# board.net
KiCad netlist of a schematic drawn in EAGLE
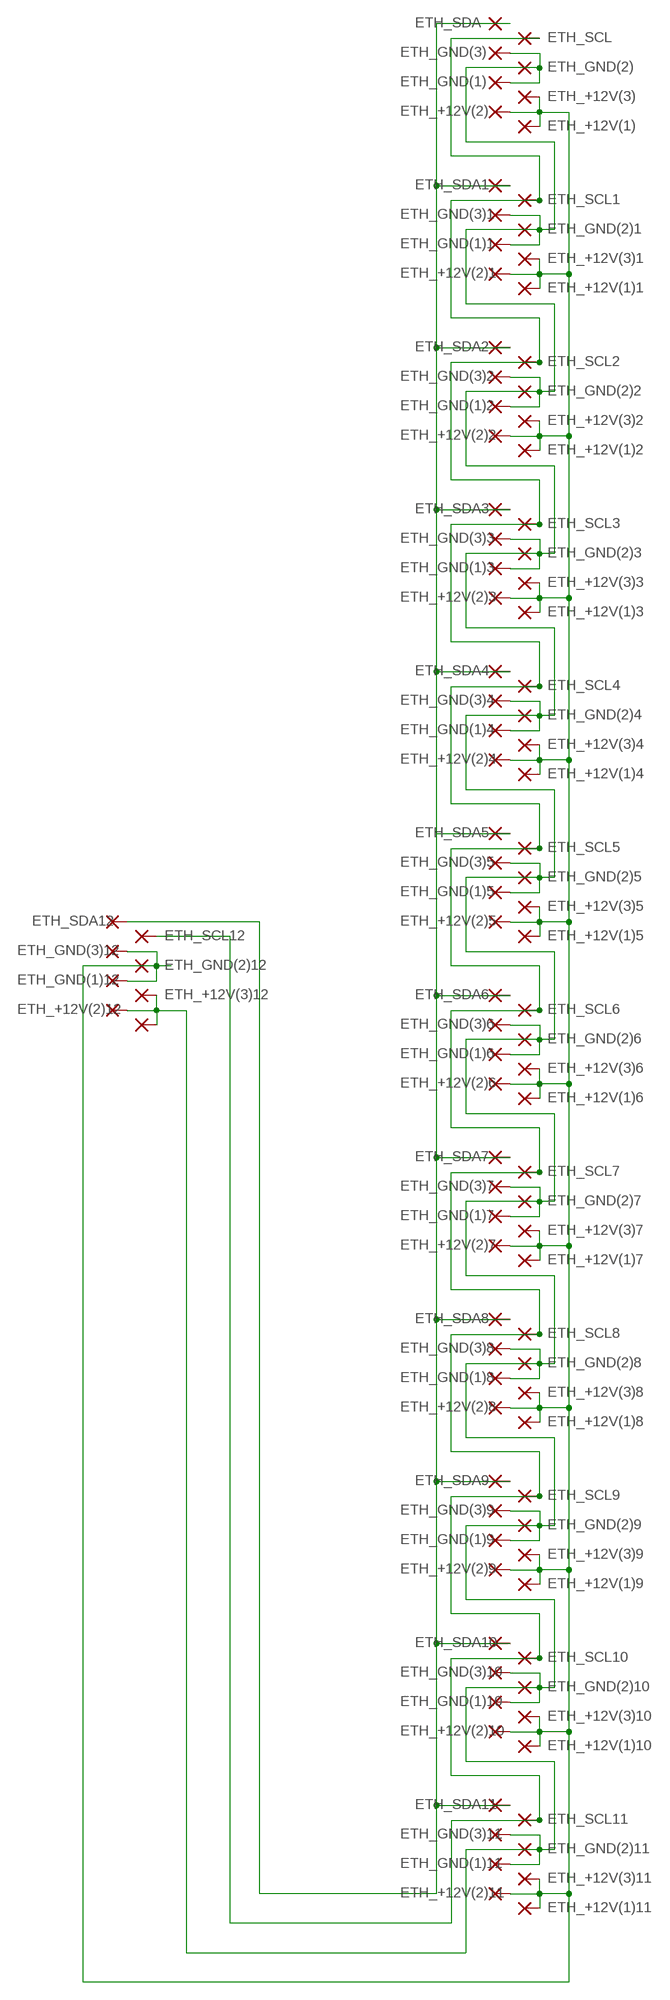
[diagram p0: schematic, sheet 1]

(export (version "E")
  (design (tool "Eeschema 10.0.6"))
  (components
    (comp (ref "ETH_+12V(1)")
      (value "2,15/1,0")
      (footprint "eagle-import:2,15_1,0")
      (libsource (lib "eagle-import") (part "2,15/1,0"))
    )
    (comp (ref "ETH_+12V(1)1")
      (value "2,15/1,0")
      (footprint "eagle-import:2,15_1,0")
      (libsource (lib "eagle-import") (part "2,15/1,0"))
    )
    (comp (ref "ETH_+12V(1)2")
      (value "2,15/1,0")
      (footprint "eagle-import:2,15_1,0")
      (libsource (lib "eagle-import") (part "2,15/1,0"))
    )
    (comp (ref "ETH_+12V(1)3")
      (value "2,15/1,0")
      (footprint "eagle-import:2,15_1,0")
      (libsource (lib "eagle-import") (part "2,15/1,0"))
    )
    (comp (ref "ETH_+12V(1)4")
      (value "2,15/1,0")
      (footprint "eagle-import:2,15_1,0")
      (libsource (lib "eagle-import") (part "2,15/1,0"))
    )
    (comp (ref "ETH_+12V(1)5")
      (value "2,15/1,0")
      (footprint "eagle-import:2,15_1,0")
      (libsource (lib "eagle-import") (part "2,15/1,0"))
    )
    (comp (ref "ETH_+12V(1)6")
      (value "2,15/1,0")
      (footprint "eagle-import:2,15_1,0")
      (libsource (lib "eagle-import") (part "2,15/1,0"))
    )
    (comp (ref "ETH_+12V(1)7")
      (value "2,15/1,0")
      (footprint "eagle-import:2,15_1,0")
      (libsource (lib "eagle-import") (part "2,15/1,0"))
    )
    (comp (ref "ETH_+12V(1)8")
      (value "2,15/1,0")
      (footprint "eagle-import:2,15_1,0")
      (libsource (lib "eagle-import") (part "2,15/1,0"))
    )
    (comp (ref "ETH_+12V(1)9")
      (value "2,15/1,0")
      (footprint "eagle-import:2,15_1,0")
      (libsource (lib "eagle-import") (part "2,15/1,0"))
    )
    (comp (ref "ETH_+12V(1)10")
      (value "2,15/1,0")
      (footprint "eagle-import:2,15_1,0")
      (libsource (lib "eagle-import") (part "2,15/1,0"))
    )
    (comp (ref "ETH_+12V(1)11")
      (value "2,15/1,0")
      (footprint "eagle-import:2,15_1,0")
      (libsource (lib "eagle-import") (part "2,15/1,0"))
    )
    (comp (ref "ETH_+12V(1)12")
      (value "2,15/1,0")
      (footprint "eagle-import:2,15_1,0")
      (libsource (lib "eagle-import") (part "2,15/1,0"))
    )
    (comp (ref "ETH_+12V(2)")
      (value "2,15/1,0")
      (footprint "eagle-import:2,15_1,0")
      (libsource (lib "eagle-import") (part "2,15/1,0"))
    )
    (comp (ref "ETH_+12V(2)1")
      (value "2,15/1,0")
      (footprint "eagle-import:2,15_1,0")
      (libsource (lib "eagle-import") (part "2,15/1,0"))
    )
    (comp (ref "ETH_+12V(2)2")
      (value "2,15/1,0")
      (footprint "eagle-import:2,15_1,0")
      (libsource (lib "eagle-import") (part "2,15/1,0"))
    )
    (comp (ref "ETH_+12V(2)3")
      (value "2,15/1,0")
      (footprint "eagle-import:2,15_1,0")
      (libsource (lib "eagle-import") (part "2,15/1,0"))
    )
    (comp (ref "ETH_+12V(2)4")
      (value "2,15/1,0")
      (footprint "eagle-import:2,15_1,0")
      (libsource (lib "eagle-import") (part "2,15/1,0"))
    )
    (comp (ref "ETH_+12V(2)5")
      (value "2,15/1,0")
      (footprint "eagle-import:2,15_1,0")
      (libsource (lib "eagle-import") (part "2,15/1,0"))
    )
    (comp (ref "ETH_+12V(2)6")
      (value "2,15/1,0")
      (footprint "eagle-import:2,15_1,0")
      (libsource (lib "eagle-import") (part "2,15/1,0"))
    )
    (comp (ref "ETH_+12V(2)7")
      (value "2,15/1,0")
      (footprint "eagle-import:2,15_1,0")
      (libsource (lib "eagle-import") (part "2,15/1,0"))
    )
    (comp (ref "ETH_+12V(2)8")
      (value "2,15/1,0")
      (footprint "eagle-import:2,15_1,0")
      (libsource (lib "eagle-import") (part "2,15/1,0"))
    )
    (comp (ref "ETH_+12V(2)9")
      (value "2,15/1,0")
      (footprint "eagle-import:2,15_1,0")
      (libsource (lib "eagle-import") (part "2,15/1,0"))
    )
    (comp (ref "ETH_+12V(2)10")
      (value "2,15/1,0")
      (footprint "eagle-import:2,15_1,0")
      (libsource (lib "eagle-import") (part "2,15/1,0"))
    )
    (comp (ref "ETH_+12V(2)11")
      (value "2,15/1,0")
      (footprint "eagle-import:2,15_1,0")
      (libsource (lib "eagle-import") (part "2,15/1,0"))
    )
    (comp (ref "ETH_+12V(2)12")
      (value "2,15/1,0")
      (footprint "eagle-import:2,15_1,0")
      (libsource (lib "eagle-import") (part "2,15/1,0"))
    )
    (comp (ref "ETH_+12V(3)")
      (value "2,15/1,0")
      (footprint "eagle-import:2,15_1,0")
      (libsource (lib "eagle-import") (part "2,15/1,0"))
    )
    (comp (ref "ETH_+12V(3)1")
      (value "2,15/1,0")
      (footprint "eagle-import:2,15_1,0")
      (libsource (lib "eagle-import") (part "2,15/1,0"))
    )
    (comp (ref "ETH_+12V(3)2")
      (value "2,15/1,0")
      (footprint "eagle-import:2,15_1,0")
      (libsource (lib "eagle-import") (part "2,15/1,0"))
    )
    (comp (ref "ETH_+12V(3)3")
      (value "2,15/1,0")
      (footprint "eagle-import:2,15_1,0")
      (libsource (lib "eagle-import") (part "2,15/1,0"))
    )
    (comp (ref "ETH_+12V(3)4")
      (value "2,15/1,0")
      (footprint "eagle-import:2,15_1,0")
      (libsource (lib "eagle-import") (part "2,15/1,0"))
    )
    (comp (ref "ETH_+12V(3)5")
      (value "2,15/1,0")
      (footprint "eagle-import:2,15_1,0")
      (libsource (lib "eagle-import") (part "2,15/1,0"))
    )
    (comp (ref "ETH_+12V(3)6")
      (value "2,15/1,0")
      (footprint "eagle-import:2,15_1,0")
      (libsource (lib "eagle-import") (part "2,15/1,0"))
    )
    (comp (ref "ETH_+12V(3)7")
      (value "2,15/1,0")
      (footprint "eagle-import:2,15_1,0")
      (libsource (lib "eagle-import") (part "2,15/1,0"))
    )
    (comp (ref "ETH_+12V(3)8")
      (value "2,15/1,0")
      (footprint "eagle-import:2,15_1,0")
      (libsource (lib "eagle-import") (part "2,15/1,0"))
    )
    (comp (ref "ETH_+12V(3)9")
      (value "2,15/1,0")
      (footprint "eagle-import:2,15_1,0")
      (libsource (lib "eagle-import") (part "2,15/1,0"))
    )
    (comp (ref "ETH_+12V(3)10")
      (value "2,15/1,0")
      (footprint "eagle-import:2,15_1,0")
      (libsource (lib "eagle-import") (part "2,15/1,0"))
    )
    (comp (ref "ETH_+12V(3)11")
      (value "2,15/1,0")
      (footprint "eagle-import:2,15_1,0")
      (libsource (lib "eagle-import") (part "2,15/1,0"))
    )
    (comp (ref "ETH_+12V(3)12")
      (value "2,15/1,0")
      (footprint "eagle-import:2,15_1,0")
      (libsource (lib "eagle-import") (part "2,15/1,0"))
    )
    (comp (ref "ETH_GND(1)")
      (value "2,15/1,0")
      (footprint "eagle-import:2,15_1,0")
      (libsource (lib "eagle-import") (part "2,15/1,0"))
    )
    (comp (ref "ETH_GND(1)1")
      (value "2,15/1,0")
      (footprint "eagle-import:2,15_1,0")
      (libsource (lib "eagle-import") (part "2,15/1,0"))
    )
    (comp (ref "ETH_GND(1)2")
      (value "2,15/1,0")
      (footprint "eagle-import:2,15_1,0")
      (libsource (lib "eagle-import") (part "2,15/1,0"))
    )
    (comp (ref "ETH_GND(1)3")
      (value "2,15/1,0")
      (footprint "eagle-import:2,15_1,0")
      (libsource (lib "eagle-import") (part "2,15/1,0"))
    )
    (comp (ref "ETH_GND(1)4")
      (value "2,15/1,0")
      (footprint "eagle-import:2,15_1,0")
      (libsource (lib "eagle-import") (part "2,15/1,0"))
    )
    (comp (ref "ETH_GND(1)5")
      (value "2,15/1,0")
      (footprint "eagle-import:2,15_1,0")
      (libsource (lib "eagle-import") (part "2,15/1,0"))
    )
    (comp (ref "ETH_GND(1)6")
      (value "2,15/1,0")
      (footprint "eagle-import:2,15_1,0")
      (libsource (lib "eagle-import") (part "2,15/1,0"))
    )
    (comp (ref "ETH_GND(1)7")
      (value "2,15/1,0")
      (footprint "eagle-import:2,15_1,0")
      (libsource (lib "eagle-import") (part "2,15/1,0"))
    )
    (comp (ref "ETH_GND(1)8")
      (value "2,15/1,0")
      (footprint "eagle-import:2,15_1,0")
      (libsource (lib "eagle-import") (part "2,15/1,0"))
    )
    (comp (ref "ETH_GND(1)9")
      (value "2,15/1,0")
      (footprint "eagle-import:2,15_1,0")
      (libsource (lib "eagle-import") (part "2,15/1,0"))
    )
    (comp (ref "ETH_GND(1)10")
      (value "2,15/1,0")
      (footprint "eagle-import:2,15_1,0")
      (libsource (lib "eagle-import") (part "2,15/1,0"))
    )
    (comp (ref "ETH_GND(1)11")
      (value "2,15/1,0")
      (footprint "eagle-import:2,15_1,0")
      (libsource (lib "eagle-import") (part "2,15/1,0"))
    )
    (comp (ref "ETH_GND(1)12")
      (value "2,15/1,0")
      (footprint "eagle-import:2,15_1,0")
      (libsource (lib "eagle-import") (part "2,15/1,0"))
    )
    (comp (ref "ETH_GND(2)")
      (value "2,15/1,0")
      (footprint "eagle-import:2,15_1,0")
      (libsource (lib "eagle-import") (part "2,15/1,0"))
    )
    (comp (ref "ETH_GND(2)1")
      (value "2,15/1,0")
      (footprint "eagle-import:2,15_1,0")
      (libsource (lib "eagle-import") (part "2,15/1,0"))
    )
    (comp (ref "ETH_GND(2)2")
      (value "2,15/1,0")
      (footprint "eagle-import:2,15_1,0")
      (libsource (lib "eagle-import") (part "2,15/1,0"))
    )
    (comp (ref "ETH_GND(2)3")
      (value "2,15/1,0")
      (footprint "eagle-import:2,15_1,0")
      (libsource (lib "eagle-import") (part "2,15/1,0"))
    )
    (comp (ref "ETH_GND(2)4")
      (value "2,15/1,0")
      (footprint "eagle-import:2,15_1,0")
      (libsource (lib "eagle-import") (part "2,15/1,0"))
    )
    (comp (ref "ETH_GND(2)5")
      (value "2,15/1,0")
      (footprint "eagle-import:2,15_1,0")
      (libsource (lib "eagle-import") (part "2,15/1,0"))
    )
    (comp (ref "ETH_GND(2)6")
      (value "2,15/1,0")
      (footprint "eagle-import:2,15_1,0")
      (libsource (lib "eagle-import") (part "2,15/1,0"))
    )
    (comp (ref "ETH_GND(2)7")
      (value "2,15/1,0")
      (footprint "eagle-import:2,15_1,0")
      (libsource (lib "eagle-import") (part "2,15/1,0"))
    )
    (comp (ref "ETH_GND(2)8")
      (value "2,15/1,0")
      (footprint "eagle-import:2,15_1,0")
      (libsource (lib "eagle-import") (part "2,15/1,0"))
    )
    (comp (ref "ETH_GND(2)9")
      (value "2,15/1,0")
      (footprint "eagle-import:2,15_1,0")
      (libsource (lib "eagle-import") (part "2,15/1,0"))
    )
    (comp (ref "ETH_GND(2)10")
      (value "2,15/1,0")
      (footprint "eagle-import:2,15_1,0")
      (libsource (lib "eagle-import") (part "2,15/1,0"))
    )
    (comp (ref "ETH_GND(2)11")
      (value "2,15/1,0")
      (footprint "eagle-import:2,15_1,0")
      (libsource (lib "eagle-import") (part "2,15/1,0"))
    )
    (comp (ref "ETH_GND(2)12")
      (value "2,15/1,0")
      (footprint "eagle-import:2,15_1,0")
      (libsource (lib "eagle-import") (part "2,15/1,0"))
    )
    (comp (ref "ETH_GND(3)")
      (value "2,15/1,0")
      (footprint "eagle-import:2,15_1,0")
      (libsource (lib "eagle-import") (part "2,15/1,0"))
    )
    (comp (ref "ETH_GND(3)1")
      (value "2,15/1,0")
      (footprint "eagle-import:2,15_1,0")
      (libsource (lib "eagle-import") (part "2,15/1,0"))
    )
    (comp (ref "ETH_GND(3)2")
      (value "2,15/1,0")
      (footprint "eagle-import:2,15_1,0")
      (libsource (lib "eagle-import") (part "2,15/1,0"))
    )
    (comp (ref "ETH_GND(3)3")
      (value "2,15/1,0")
      (footprint "eagle-import:2,15_1,0")
      (libsource (lib "eagle-import") (part "2,15/1,0"))
    )
    (comp (ref "ETH_GND(3)4")
      (value "2,15/1,0")
      (footprint "eagle-import:2,15_1,0")
      (libsource (lib "eagle-import") (part "2,15/1,0"))
    )
    (comp (ref "ETH_GND(3)5")
      (value "2,15/1,0")
      (footprint "eagle-import:2,15_1,0")
      (libsource (lib "eagle-import") (part "2,15/1,0"))
    )
    (comp (ref "ETH_GND(3)6")
      (value "2,15/1,0")
      (footprint "eagle-import:2,15_1,0")
      (libsource (lib "eagle-import") (part "2,15/1,0"))
    )
    (comp (ref "ETH_GND(3)7")
      (value "2,15/1,0")
      (footprint "eagle-import:2,15_1,0")
      (libsource (lib "eagle-import") (part "2,15/1,0"))
    )
    (comp (ref "ETH_GND(3)8")
      (value "2,15/1,0")
      (footprint "eagle-import:2,15_1,0")
      (libsource (lib "eagle-import") (part "2,15/1,0"))
    )
    (comp (ref "ETH_GND(3)9")
      (value "2,15/1,0")
      (footprint "eagle-import:2,15_1,0")
      (libsource (lib "eagle-import") (part "2,15/1,0"))
    )
    (comp (ref "ETH_GND(3)10")
      (value "2,15/1,0")
      (footprint "eagle-import:2,15_1,0")
      (libsource (lib "eagle-import") (part "2,15/1,0"))
    )
    (comp (ref "ETH_GND(3)11")
      (value "2,15/1,0")
      (footprint "eagle-import:2,15_1,0")
      (libsource (lib "eagle-import") (part "2,15/1,0"))
    )
    (comp (ref "ETH_GND(3)12")
      (value "2,15/1,0")
      (footprint "eagle-import:2,15_1,0")
      (libsource (lib "eagle-import") (part "2,15/1,0"))
    )
    (comp (ref "ETH_SCL")
      (value "2,15/1,0")
      (footprint "eagle-import:2,15_1,0")
      (libsource (lib "eagle-import") (part "2,15/1,0"))
    )
    (comp (ref "ETH_SCL1")
      (value "2,15/1,0")
      (footprint "eagle-import:2,15_1,0")
      (libsource (lib "eagle-import") (part "2,15/1,0"))
    )
    (comp (ref "ETH_SCL2")
      (value "2,15/1,0")
      (footprint "eagle-import:2,15_1,0")
      (libsource (lib "eagle-import") (part "2,15/1,0"))
    )
    (comp (ref "ETH_SCL3")
      (value "2,15/1,0")
      (footprint "eagle-import:2,15_1,0")
      (libsource (lib "eagle-import") (part "2,15/1,0"))
    )
    (comp (ref "ETH_SCL4")
      (value "2,15/1,0")
      (footprint "eagle-import:2,15_1,0")
      (libsource (lib "eagle-import") (part "2,15/1,0"))
    )
    (comp (ref "ETH_SCL5")
      (value "2,15/1,0")
      (footprint "eagle-import:2,15_1,0")
      (libsource (lib "eagle-import") (part "2,15/1,0"))
    )
    (comp (ref "ETH_SCL6")
      (value "2,15/1,0")
      (footprint "eagle-import:2,15_1,0")
      (libsource (lib "eagle-import") (part "2,15/1,0"))
    )
    (comp (ref "ETH_SCL7")
      (value "2,15/1,0")
      (footprint "eagle-import:2,15_1,0")
      (libsource (lib "eagle-import") (part "2,15/1,0"))
    )
    (comp (ref "ETH_SCL8")
      (value "2,15/1,0")
      (footprint "eagle-import:2,15_1,0")
      (libsource (lib "eagle-import") (part "2,15/1,0"))
    )
    (comp (ref "ETH_SCL9")
      (value "2,15/1,0")
      (footprint "eagle-import:2,15_1,0")
      (libsource (lib "eagle-import") (part "2,15/1,0"))
    )
    (comp (ref "ETH_SCL10")
      (value "2,15/1,0")
      (footprint "eagle-import:2,15_1,0")
      (libsource (lib "eagle-import") (part "2,15/1,0"))
    )
    (comp (ref "ETH_SCL11")
      (value "2,15/1,0")
      (footprint "eagle-import:2,15_1,0")
      (libsource (lib "eagle-import") (part "2,15/1,0"))
    )
    (comp (ref "ETH_SCL12")
      (value "2,15/1,0")
      (footprint "eagle-import:2,15_1,0")
      (libsource (lib "eagle-import") (part "2,15/1,0"))
    )
    (comp (ref "ETH_SDA")
      (value "2,15/1,0")
      (footprint "eagle-import:2,15_1,0")
      (libsource (lib "eagle-import") (part "2,15/1,0"))
    )
    (comp (ref "ETH_SDA1")
      (value "2,15/1,0")
      (footprint "eagle-import:2,15_1,0")
      (libsource (lib "eagle-import") (part "2,15/1,0"))
    )
    (comp (ref "ETH_SDA2")
      (value "2,15/1,0")
      (footprint "eagle-import:2,15_1,0")
      (libsource (lib "eagle-import") (part "2,15/1,0"))
    )
    (comp (ref "ETH_SDA3")
      (value "2,15/1,0")
      (footprint "eagle-import:2,15_1,0")
      (libsource (lib "eagle-import") (part "2,15/1,0"))
    )
    (comp (ref "ETH_SDA4")
      (value "2,15/1,0")
      (footprint "eagle-import:2,15_1,0")
      (libsource (lib "eagle-import") (part "2,15/1,0"))
    )
    (comp (ref "ETH_SDA5")
      (value "2,15/1,0")
      (footprint "eagle-import:2,15_1,0")
      (libsource (lib "eagle-import") (part "2,15/1,0"))
    )
    (comp (ref "ETH_SDA6")
      (value "2,15/1,0")
      (footprint "eagle-import:2,15_1,0")
      (libsource (lib "eagle-import") (part "2,15/1,0"))
    )
    (comp (ref "ETH_SDA7")
      (value "2,15/1,0")
      (footprint "eagle-import:2,15_1,0")
      (libsource (lib "eagle-import") (part "2,15/1,0"))
    )
    (comp (ref "ETH_SDA8")
      (value "2,15/1,0")
      (footprint "eagle-import:2,15_1,0")
      (libsource (lib "eagle-import") (part "2,15/1,0"))
    )
    (comp (ref "ETH_SDA9")
      (value "2,15/1,0")
      (footprint "eagle-import:2,15_1,0")
      (libsource (lib "eagle-import") (part "2,15/1,0"))
    )
    (comp (ref "ETH_SDA10")
      (value "2,15/1,0")
      (footprint "eagle-import:2,15_1,0")
      (libsource (lib "eagle-import") (part "2,15/1,0"))
    )
    (comp (ref "ETH_SDA11")
      (value "2,15/1,0")
      (footprint "eagle-import:2,15_1,0")
      (libsource (lib "eagle-import") (part "2,15/1,0"))
    )
    (comp (ref "ETH_SDA12")
      (value "2,15/1,0")
      (footprint "eagle-import:2,15_1,0")
      (libsource (lib "eagle-import") (part "2,15/1,0"))
    )
  )
  (nets
    (net (code "1") (name "Net-(ETH_+12V(1)-P)") (class "Default")
      (node (ref "ETH_+12V(1)") (pin "1") (pinfunction "P_1") (pintype "passive"))
      (node (ref "ETH_+12V(1)1") (pin "1") (pinfunction "P_1") (pintype "passive"))
      (node (ref "ETH_+12V(1)10") (pin "1") (pinfunction "P_1") (pintype "passive"))
      (node (ref "ETH_+12V(1)11") (pin "1") (pinfunction "P_1") (pintype "passive"))
      (node (ref "ETH_+12V(1)2") (pin "1") (pinfunction "P_1") (pintype "passive"))
      (node (ref "ETH_+12V(1)3") (pin "1") (pinfunction "P_1") (pintype "passive"))
      (node (ref "ETH_+12V(1)4") (pin "1") (pinfunction "P_1") (pintype "passive"))
      (node (ref "ETH_+12V(1)5") (pin "1") (pinfunction "P_1") (pintype "passive"))
      (node (ref "ETH_+12V(1)6") (pin "1") (pinfunction "P_1") (pintype "passive"))
      (node (ref "ETH_+12V(1)7") (pin "1") (pinfunction "P_1") (pintype "passive"))
      (node (ref "ETH_+12V(1)8") (pin "1") (pinfunction "P_1") (pintype "passive"))
      (node (ref "ETH_+12V(1)9") (pin "1") (pinfunction "P_1") (pintype "passive"))
      (node (ref "ETH_+12V(2)") (pin "1") (pinfunction "P_1") (pintype "passive"))
      (node (ref "ETH_+12V(2)1") (pin "1") (pinfunction "P_1") (pintype "passive"))
      (node (ref "ETH_+12V(2)10") (pin "1") (pinfunction "P_1") (pintype "passive"))
      (node (ref "ETH_+12V(2)11") (pin "1") (pinfunction "P_1") (pintype "passive"))
      (node (ref "ETH_+12V(2)2") (pin "1") (pinfunction "P_1") (pintype "passive"))
      (node (ref "ETH_+12V(2)3") (pin "1") (pinfunction "P_1") (pintype "passive"))
      (node (ref "ETH_+12V(2)4") (pin "1") (pinfunction "P_1") (pintype "passive"))
      (node (ref "ETH_+12V(2)5") (pin "1") (pinfunction "P_1") (pintype "passive"))
      (node (ref "ETH_+12V(2)6") (pin "1") (pinfunction "P_1") (pintype "passive"))
      (node (ref "ETH_+12V(2)7") (pin "1") (pinfunction "P_1") (pintype "passive"))
      (node (ref "ETH_+12V(2)8") (pin "1") (pinfunction "P_1") (pintype "passive"))
      (node (ref "ETH_+12V(2)9") (pin "1") (pinfunction "P_1") (pintype "passive"))
      (node (ref "ETH_+12V(3)") (pin "1") (pinfunction "P_1") (pintype "passive"))
      (node (ref "ETH_+12V(3)1") (pin "1") (pinfunction "P_1") (pintype "passive"))
      (node (ref "ETH_+12V(3)10") (pin "1") (pinfunction "P_1") (pintype "passive"))
      (node (ref "ETH_+12V(3)11") (pin "1") (pinfunction "P_1") (pintype "passive"))
      (node (ref "ETH_+12V(3)2") (pin "1") (pinfunction "P_1") (pintype "passive"))
      (node (ref "ETH_+12V(3)3") (pin "1") (pinfunction "P_1") (pintype "passive"))
      (node (ref "ETH_+12V(3)4") (pin "1") (pinfunction "P_1") (pintype "passive"))
      (node (ref "ETH_+12V(3)5") (pin "1") (pinfunction "P_1") (pintype "passive"))
      (node (ref "ETH_+12V(3)6") (pin "1") (pinfunction "P_1") (pintype "passive"))
      (node (ref "ETH_+12V(3)7") (pin "1") (pinfunction "P_1") (pintype "passive"))
      (node (ref "ETH_+12V(3)8") (pin "1") (pinfunction "P_1") (pintype "passive"))
      (node (ref "ETH_+12V(3)9") (pin "1") (pinfunction "P_1") (pintype "passive"))
      (node (ref "ETH_GND(1)12") (pin "1") (pinfunction "P_1") (pintype "passive"))
      (node (ref "ETH_GND(2)12") (pin "1") (pinfunction "P_1") (pintype "passive"))
      (node (ref "ETH_GND(3)12") (pin "1") (pinfunction "P_1") (pintype "passive"))
    )
    (net (code "2") (name "Net-(ETH_+12V(1)12-P)") (class "Default")
      (node (ref "ETH_+12V(1)12") (pin "1") (pinfunction "P_1") (pintype "passive"))
      (node (ref "ETH_+12V(2)12") (pin "1") (pinfunction "P_1") (pintype "passive"))
      (node (ref "ETH_+12V(3)12") (pin "1") (pinfunction "P_1") (pintype "passive"))
      (node (ref "ETH_GND(1)") (pin "1") (pinfunction "P_1") (pintype "passive"))
      (node (ref "ETH_GND(1)1") (pin "1") (pinfunction "P_1") (pintype "passive"))
      (node (ref "ETH_GND(1)10") (pin "1") (pinfunction "P_1") (pintype "passive"))
      (node (ref "ETH_GND(1)11") (pin "1") (pinfunction "P_1") (pintype "passive"))
      (node (ref "ETH_GND(1)2") (pin "1") (pinfunction "P_1") (pintype "passive"))
      (node (ref "ETH_GND(1)3") (pin "1") (pinfunction "P_1") (pintype "passive"))
      (node (ref "ETH_GND(1)4") (pin "1") (pinfunction "P_1") (pintype "passive"))
      (node (ref "ETH_GND(1)5") (pin "1") (pinfunction "P_1") (pintype "passive"))
      (node (ref "ETH_GND(1)6") (pin "1") (pinfunction "P_1") (pintype "passive"))
      (node (ref "ETH_GND(1)7") (pin "1") (pinfunction "P_1") (pintype "passive"))
      (node (ref "ETH_GND(1)8") (pin "1") (pinfunction "P_1") (pintype "passive"))
      (node (ref "ETH_GND(1)9") (pin "1") (pinfunction "P_1") (pintype "passive"))
      (node (ref "ETH_GND(2)") (pin "1") (pinfunction "P_1") (pintype "passive"))
      (node (ref "ETH_GND(2)1") (pin "1") (pinfunction "P_1") (pintype "passive"))
      (node (ref "ETH_GND(2)10") (pin "1") (pinfunction "P_1") (pintype "passive"))
      (node (ref "ETH_GND(2)11") (pin "1") (pinfunction "P_1") (pintype "passive"))
      (node (ref "ETH_GND(2)2") (pin "1") (pinfunction "P_1") (pintype "passive"))
      (node (ref "ETH_GND(2)3") (pin "1") (pinfunction "P_1") (pintype "passive"))
      (node (ref "ETH_GND(2)4") (pin "1") (pinfunction "P_1") (pintype "passive"))
      (node (ref "ETH_GND(2)5") (pin "1") (pinfunction "P_1") (pintype "passive"))
      (node (ref "ETH_GND(2)6") (pin "1") (pinfunction "P_1") (pintype "passive"))
      (node (ref "ETH_GND(2)7") (pin "1") (pinfunction "P_1") (pintype "passive"))
      (node (ref "ETH_GND(2)8") (pin "1") (pinfunction "P_1") (pintype "passive"))
      (node (ref "ETH_GND(2)9") (pin "1") (pinfunction "P_1") (pintype "passive"))
      (node (ref "ETH_GND(3)") (pin "1") (pinfunction "P_1") (pintype "passive"))
      (node (ref "ETH_GND(3)1") (pin "1") (pinfunction "P_1") (pintype "passive"))
      (node (ref "ETH_GND(3)10") (pin "1") (pinfunction "P_1") (pintype "passive"))
      (node (ref "ETH_GND(3)11") (pin "1") (pinfunction "P_1") (pintype "passive"))
      (node (ref "ETH_GND(3)2") (pin "1") (pinfunction "P_1") (pintype "passive"))
      (node (ref "ETH_GND(3)3") (pin "1") (pinfunction "P_1") (pintype "passive"))
      (node (ref "ETH_GND(3)4") (pin "1") (pinfunction "P_1") (pintype "passive"))
      (node (ref "ETH_GND(3)5") (pin "1") (pinfunction "P_1") (pintype "passive"))
      (node (ref "ETH_GND(3)6") (pin "1") (pinfunction "P_1") (pintype "passive"))
      (node (ref "ETH_GND(3)7") (pin "1") (pinfunction "P_1") (pintype "passive"))
      (node (ref "ETH_GND(3)8") (pin "1") (pinfunction "P_1") (pintype "passive"))
      (node (ref "ETH_GND(3)9") (pin "1") (pinfunction "P_1") (pintype "passive"))
    )
    (net (code "3") (name "Net-(ETH_SCL-P)") (class "Default")
      (node (ref "ETH_SCL") (pin "1") (pinfunction "P_1") (pintype "passive"))
      (node (ref "ETH_SCL1") (pin "1") (pinfunction "P_1") (pintype "passive"))
      (node (ref "ETH_SCL10") (pin "1") (pinfunction "P_1") (pintype "passive"))
      (node (ref "ETH_SCL11") (pin "1") (pinfunction "P_1") (pintype "passive"))
      (node (ref "ETH_SCL12") (pin "1") (pinfunction "P_1") (pintype "passive"))
      (node (ref "ETH_SCL2") (pin "1") (pinfunction "P_1") (pintype "passive"))
      (node (ref "ETH_SCL3") (pin "1") (pinfunction "P_1") (pintype "passive"))
      (node (ref "ETH_SCL4") (pin "1") (pinfunction "P_1") (pintype "passive"))
      (node (ref "ETH_SCL5") (pin "1") (pinfunction "P_1") (pintype "passive"))
      (node (ref "ETH_SCL6") (pin "1") (pinfunction "P_1") (pintype "passive"))
      (node (ref "ETH_SCL7") (pin "1") (pinfunction "P_1") (pintype "passive"))
      (node (ref "ETH_SCL8") (pin "1") (pinfunction "P_1") (pintype "passive"))
      (node (ref "ETH_SCL9") (pin "1") (pinfunction "P_1") (pintype "passive"))
    )
    (net (code "4") (name "Net-(ETH_SDA-P)") (class "Default")
      (node (ref "ETH_SDA") (pin "1") (pinfunction "P_1") (pintype "passive"))
      (node (ref "ETH_SDA1") (pin "1") (pinfunction "P_1") (pintype "passive"))
      (node (ref "ETH_SDA10") (pin "1") (pinfunction "P_1") (pintype "passive"))
      (node (ref "ETH_SDA11") (pin "1") (pinfunction "P_1") (pintype "passive"))
      (node (ref "ETH_SDA12") (pin "1") (pinfunction "P_1") (pintype "passive"))
      (node (ref "ETH_SDA2") (pin "1") (pinfunction "P_1") (pintype "passive"))
      (node (ref "ETH_SDA3") (pin "1") (pinfunction "P_1") (pintype "passive"))
      (node (ref "ETH_SDA4") (pin "1") (pinfunction "P_1") (pintype "passive"))
      (node (ref "ETH_SDA5") (pin "1") (pinfunction "P_1") (pintype "passive"))
      (node (ref "ETH_SDA6") (pin "1") (pinfunction "P_1") (pintype "passive"))
      (node (ref "ETH_SDA7") (pin "1") (pinfunction "P_1") (pintype "passive"))
      (node (ref "ETH_SDA8") (pin "1") (pinfunction "P_1") (pintype "passive"))
      (node (ref "ETH_SDA9") (pin "1") (pinfunction "P_1") (pintype "passive"))
    )
  )
)
